# 07_RS485.net
KiCad netlist of a schematic drawn in Altium Designer
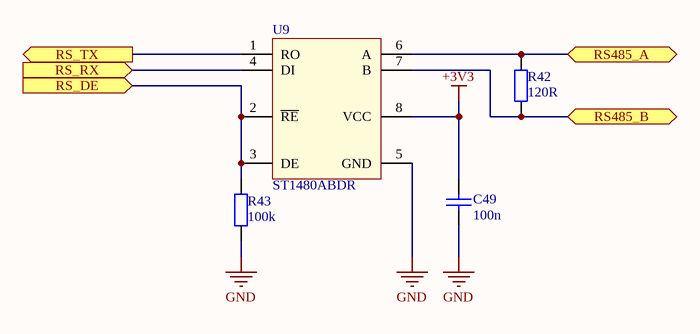
[diagram p0: 07_RS485.SchDoc]

(export (version "E")
  (design (tool "Eeschema 10.0.6"))
  (components
    (comp (ref "C49")
      (value "100n")
      (footprint "C0603_IPC_HD")
      (description "CAP CER 0.1UF 16V X7R 0603")
      (fields
        (field (name "MANUFACTURER") "Samsung Electro-Mechanics")
        (field (name "MANUFACTURER PART NUMBER") "CL10B104KO8NNNC")
      )
      (libsource (lib "alfasat_lib") (part "CL10B104KO8NNNC"))
    )
    (comp (ref "R42")
      (value "120R")
      (footprint "R0603_IPC_MD")
      (description "RES SMD 120 OHM 5% 1/10W 0603")
      (fields
        (field (name "MANUFACTURER") "Yageo")
        (field (name "MANUFACTURER PART NUMBER") "RC0603JR-07120RL")
      )
      (libsource (lib "alfasat_lib") (part "RC0603JR-07120RL"))
    )
    (comp (ref "R43")
      (value "100k")
      (footprint "R0603_IPC_MD")
      (description "RES 100K OHM 1% 1/10W 0603")
      (fields
        (field (name "MANUFACTURER") "Bourns Inc.")
        (field (name "MANUFACTURER PART NUMBER") "RMCF0603FT100K")
      )
      (libsource (lib "alfasat_lib") (part "RMCF0603FT100K"))
    )
    (comp (ref "U9")
      (value "ST1480ABDR")
      (footprint "SOIC-8")
      (description "IC TXRX 3.3V RS485/422 8 SOIC")
      (fields (field (name "MANUFACTURER") "STMicroelectronics"))
      (libsource (lib "alfasat_lib") (part "ST1480ABDR"))
    )
  )
  (nets
    (net (code "1") (name "+3V3") (class "Default")
      (node (ref "C49") (pin "2") (pinfunction "2_2") (pintype "passive"))
      (node (ref "U9") (pin "8") (pinfunction "VCC_8") (pintype "passive"))
    )
    (net (code "2") (name "/RS485_A") (class "Default")
      (node (ref "R42") (pin "2") (pinfunction "2_2") (pintype "passive"))
      (node (ref "U9") (pin "6") (pinfunction "A_6") (pintype "passive"))
    )
    (net (code "3") (name "/RS485_B") (class "Default")
      (node (ref "R42") (pin "1") (pinfunction "1_1") (pintype "passive"))
      (node (ref "U9") (pin "7") (pinfunction "B_7") (pintype "passive"))
    )
    (net (code "4") (name "/RS_DE") (class "Default")
      (node (ref "R43") (pin "2") (pinfunction "2_2") (pintype "passive"))
      (node (ref "U9") (pin "2") (pinfunction "~{RE}_2") (pintype "passive"))
      (node (ref "U9") (pin "3") (pinfunction "DE_3") (pintype "passive"))
    )
    (net (code "5") (name "/RS_RX") (class "Default")
      (node (ref "U9") (pin "4") (pinfunction "DI_4") (pintype "passive"))
    )
    (net (code "6") (name "/RS_TX") (class "Default")
      (node (ref "U9") (pin "1") (pinfunction "RO_1") (pintype "passive"))
    )
    (net (code "7") (name "GND") (class "Default")
      (node (ref "C49") (pin "1") (pinfunction "1_1") (pintype "passive"))
      (node (ref "R43") (pin "1") (pinfunction "1_1") (pintype "passive"))
      (node (ref "U9") (pin "5") (pinfunction "GND_5") (pintype "passive"))
    )
  )
)
